# UC3906_3BJT_CHARGER_2.net
KiCad netlist of a schematic drawn in EAGLE
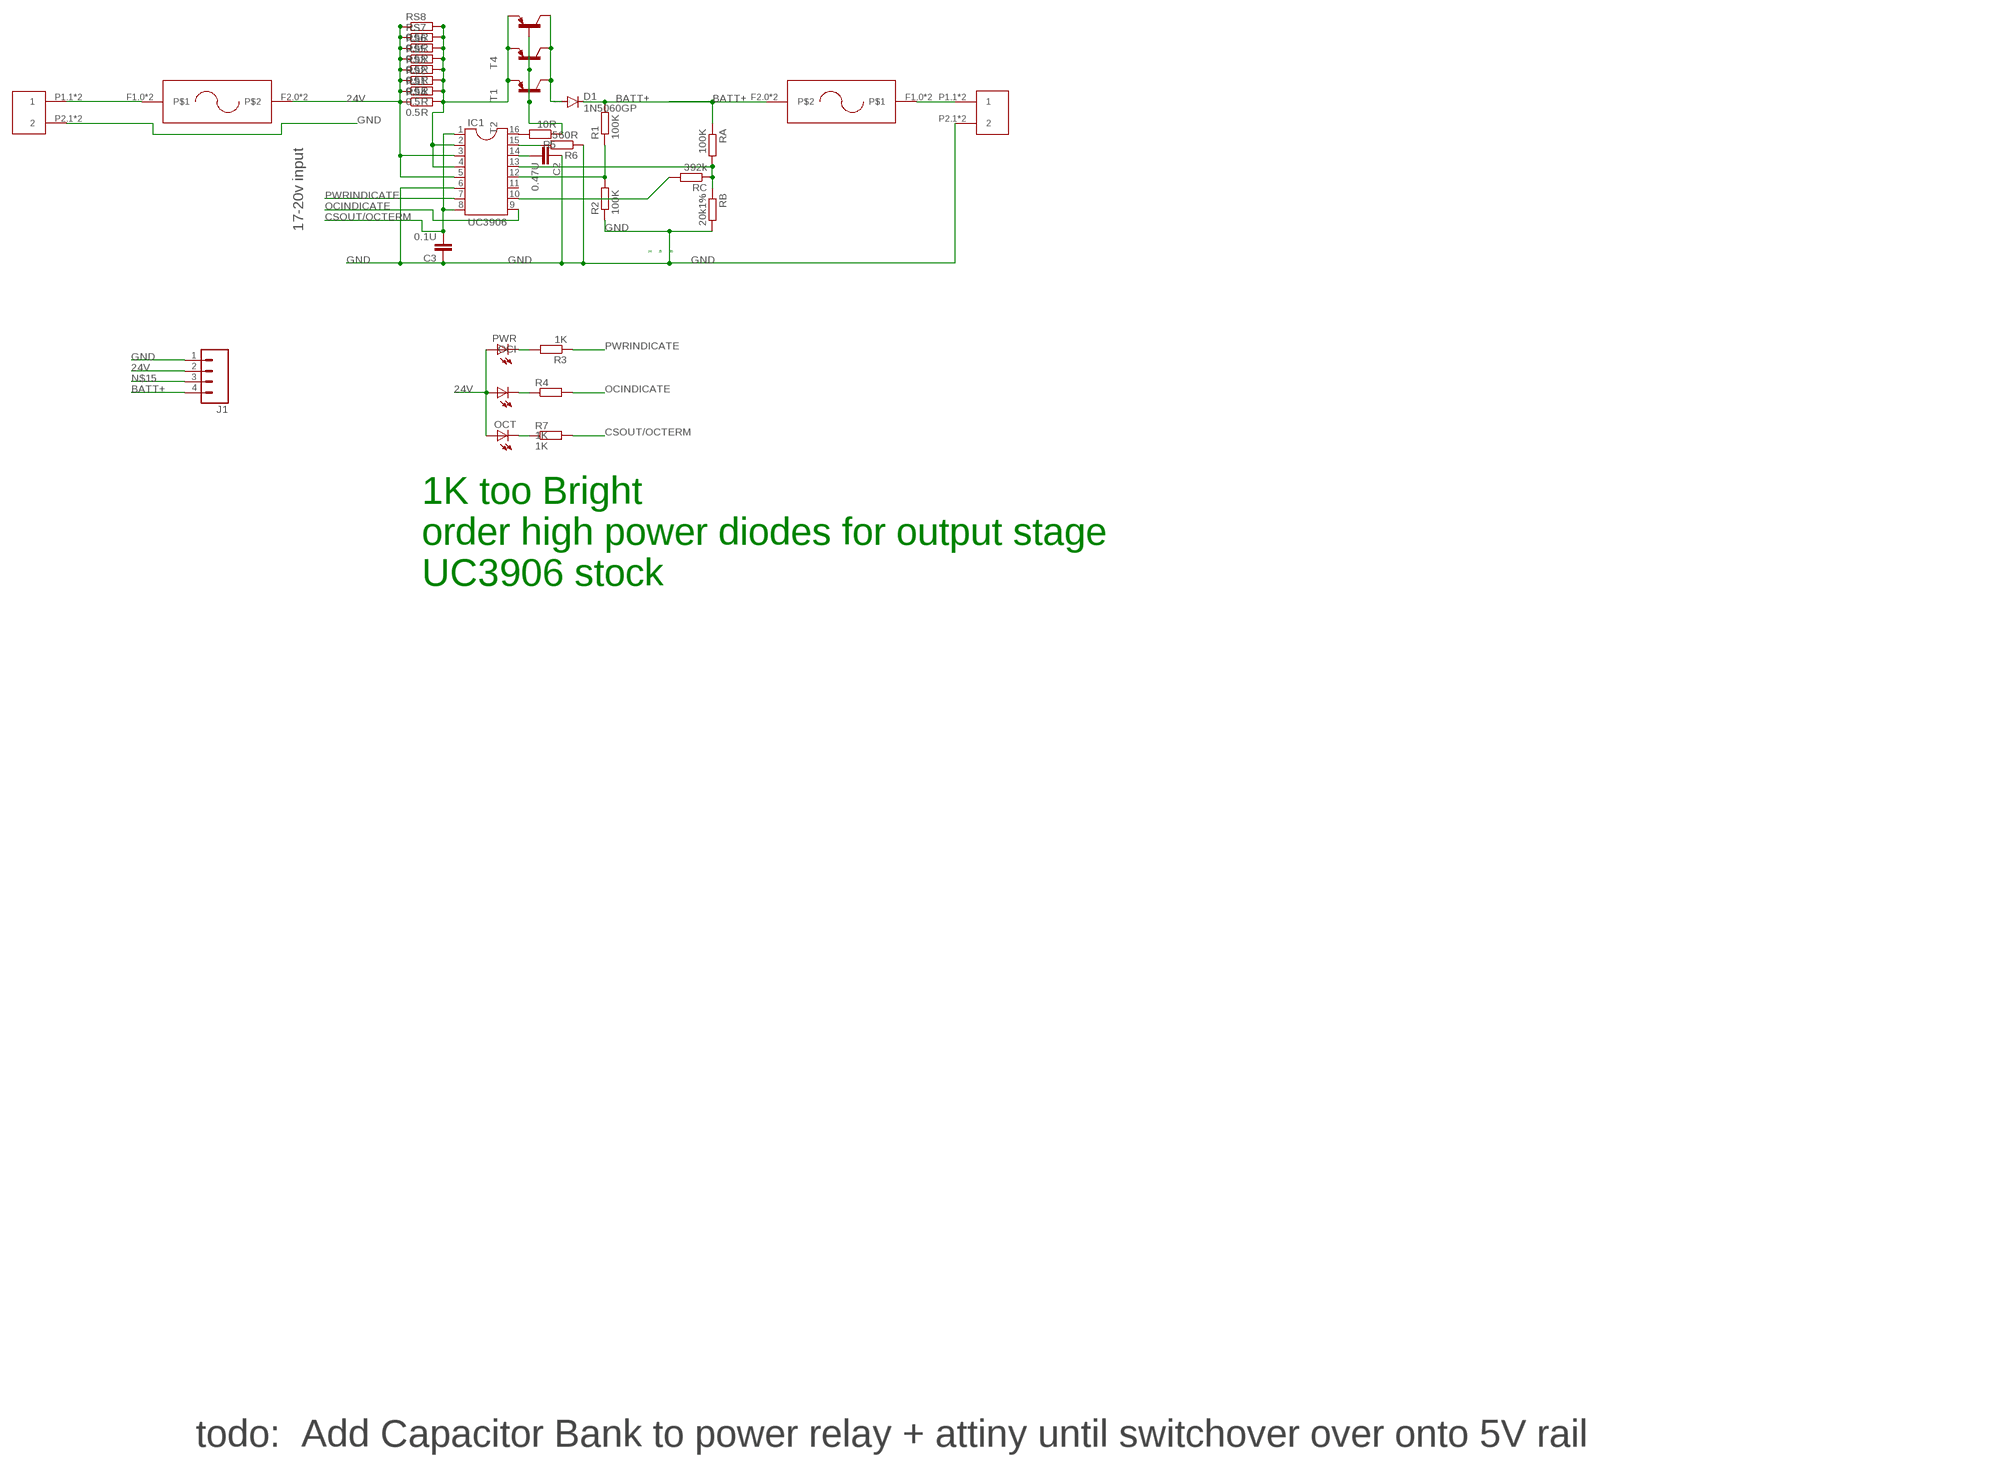
[diagram p0: schematic, sheet 1]

(export (version "E")
  (design (tool "Eeschema 10.0.6"))
  (components
    (comp (ref "BATT")
      (value "BARRIERTERMINAL")
      (footprint "eagle-import:BARRIERTERMINAL")
      (libsource (lib "eagle-import") (part "BARRIERTERMINAL"))
    )
    (comp (ref "C2")
      (value "0.47U")
      (footprint "eagle-import:C050-024X044")
      (libsource (lib "eagle-import") (part "C-EU050-024X044"))
    )
    (comp (ref "C3")
      (value "0.1U")
      (footprint "eagle-import:C050-024X044")
      (libsource (lib "eagle-import") (part "C-EU050-024X044"))
    )
    (comp (ref "D1")
      (value "1N5060GP")
      (footprint "eagle-import:DO15-12")
      (libsource (lib "eagle-import") (part "1N5060GP"))
    )
    (comp (ref "IC1")
      (value "UC3906")
      (footprint "eagle-import:DIL16")
      (libsource (lib "eagle-import") (part "DIL16"))
    )
    (comp (ref "J1")
      (value "CONN_04LONGPADS")
      (footprint "eagle-import:1X04_LONGPADS")
      (libsource (lib "eagle-import") (part "CONN_04LONGPADS"))
    )
    (comp (ref "OCI")
      (value "LED5MM")
      (footprint "eagle-import:LED5MM")
      (libsource (lib "eagle-import") (part "LED5MM"))
    )
    (comp (ref "OCT")
      (value "LED5MM")
      (footprint "eagle-import:LED5MM")
      (libsource (lib "eagle-import") (part "LED5MM"))
    )
    (comp (ref "POWERIN")
      (value "BARRIERTERMINAL")
      (footprint "eagle-import:BARRIERTERMINAL")
      (libsource (lib "eagle-import") (part "BARRIERTERMINAL"))
    )
    (comp (ref "PWR")
      (value "LED5MM")
      (footprint "eagle-import:LED5MM")
      (libsource (lib "eagle-import") (part "LED5MM"))
    )
    (comp (ref "R1")
      (value "100K")
      (footprint "eagle-import:0204_7")
      (libsource (lib "eagle-import") (part "R-EU_0204/7"))
    )
    (comp (ref "R2")
      (value "100K")
      (footprint "eagle-import:0204_7")
      (libsource (lib "eagle-import") (part "R-EU_0204/7"))
    )
    (comp (ref "R3")
      (value "1K")
      (footprint "eagle-import:0204_7")
      (libsource (lib "eagle-import") (part "R-EU_0204/7"))
    )
    (comp (ref "R4")
      (value "1K")
      (footprint "eagle-import:0204_7")
      (libsource (lib "eagle-import") (part "R-EU_0204/7"))
    )
    (comp (ref "R5")
      (value "10R")
      (footprint "eagle-import:0204_7")
      (libsource (lib "eagle-import") (part "R-EU_0204/7"))
    )
    (comp (ref "R6")
      (value "560R")
      (footprint "eagle-import:0204_7")
      (libsource (lib "eagle-import") (part "R-EU_0204/7"))
    )
    (comp (ref "R7")
      (value "1K")
      (footprint "eagle-import:0204_7")
      (libsource (lib "eagle-import") (part "R-EU_0204/7"))
    )
    (comp (ref "RA")
      (value "100K")
      (footprint "eagle-import:0204_7")
      (libsource (lib "eagle-import") (part "R-EU_0204/7"))
    )
    (comp (ref "RB")
      (value "20k1%")
      (footprint "eagle-import:0204_7")
      (libsource (lib "eagle-import") (part "R-EU_0204/7"))
    )
    (comp (ref "RC")
      (value "392k")
      (footprint "eagle-import:0204_7")
      (libsource (lib "eagle-import") (part "R-EU_0204/7"))
    )
    (comp (ref "RS1")
      (value "0.5R")
      (footprint "eagle-import:0411_15")
      (libsource (lib "eagle-import") (part "resistor_R-EU_0411/15"))
    )
    (comp (ref "RS2")
      (value "0.5R")
      (footprint "eagle-import:0411_15")
      (libsource (lib "eagle-import") (part "resistor_R-EU_0411/15"))
    )
    (comp (ref "RS3")
      (value "0.5R")
      (footprint "eagle-import:0411_15")
      (libsource (lib "eagle-import") (part "resistor_R-EU_0411/15"))
    )
    (comp (ref "RS4")
      (value "0.5R")
      (footprint "eagle-import:0411_15")
      (libsource (lib "eagle-import") (part "resistor_R-EU_0411/15"))
    )
    (comp (ref "RS5")
      (value "0.5R")
      (footprint "eagle-import:0411_15")
      (libsource (lib "eagle-import") (part "resistor_R-EU_0411/15"))
    )
    (comp (ref "RS6")
      (value "0.5R")
      (footprint "eagle-import:0411_15")
      (libsource (lib "eagle-import") (part "resistor_R-EU_0411/15"))
    )
    (comp (ref "RS7")
      (value "0.5R")
      (footprint "eagle-import:0411_15")
      (libsource (lib "eagle-import") (part "resistor_R-EU_0411/15"))
    )
    (comp (ref "RS8")
      (value "0.5R")
      (footprint "eagle-import:0411_15")
      (libsource (lib "eagle-import") (part "resistor_R-EU_0411/15"))
    )
    (comp (ref "T1")
      (value "-PNP-TO220V")
      (footprint "eagle-import:TO220V")
      (libsource (lib "eagle-import") (part "-PNP-TO220V"))
    )
    (comp (ref "T2")
      (value "-PNP-TO220V")
      (footprint "eagle-import:TO220V")
      (libsource (lib "eagle-import") (part "-PNP-TO220V"))
    )
    (comp (ref "T4")
      (value "-PNP-TO220V")
      (footprint "eagle-import:TO220V")
      (libsource (lib "eagle-import") (part "-PNP-TO220V"))
    )
    (comp (ref "U$1")
      (value "18MMFUSEHOLDER")
      (footprint "eagle-import:18MMFUSEHOLDER")
      (libsource (lib "eagle-import") (part "18MMFUSEHOLDER"))
    )
    (comp (ref "U$2")
      (value "18MMFUSEHOLDER")
      (footprint "eagle-import:18MMFUSEHOLDER")
      (libsource (lib "eagle-import") (part "18MMFUSEHOLDER"))
    )
  )
  (nets
    (net (code "1") (name "/24V") (class "Default")
      (node (ref "IC1") (pin "3") (pinfunction "3_3") (pintype "passive"))
      (node (ref "IC1") (pin "5") (pinfunction "5_5") (pintype "passive"))
      (node (ref "J1") (pin "2") (pinfunction "2_2") (pintype "passive"))
      (node (ref "OCI") (pin "A") (pinfunction "A_A") (pintype "passive"))
      (node (ref "OCT") (pin "A") (pinfunction "A_A") (pintype "passive"))
      (node (ref "PWR") (pin "A") (pinfunction "A_A") (pintype "passive"))
      (node (ref "RS1") (pin "1") (pinfunction "1_1") (pintype "passive"))
      (node (ref "RS2") (pin "1") (pinfunction "1_1") (pintype "passive"))
      (node (ref "RS3") (pin "1") (pinfunction "1_1") (pintype "passive"))
      (node (ref "RS4") (pin "1") (pinfunction "1_1") (pintype "passive"))
      (node (ref "RS5") (pin "1") (pinfunction "1_1") (pintype "passive"))
      (node (ref "RS6") (pin "1") (pinfunction "1_1") (pintype "passive"))
      (node (ref "RS7") (pin "1") (pinfunction "1_1") (pintype "passive"))
      (node (ref "RS8") (pin "1") (pinfunction "1_1") (pintype "passive"))
      (node (ref "U$2") (pin "F2.0") (pinfunction "P$2_F2.0") (pintype "bidirectional"))
      (node (ref "U$2") (pin "F2.1") (pinfunction "P$2_F2.1") (pintype "bidirectional"))
    )
    (net (code "2") (name "/BATT+") (class "Default")
      (node (ref "D1") (pin "C") (pinfunction "C_C") (pintype "passive"))
      (node (ref "J1") (pin "4") (pinfunction "4_4") (pintype "passive"))
      (node (ref "R1") (pin "2") (pinfunction "2_2") (pintype "passive"))
      (node (ref "RA") (pin "1") (pinfunction "1_1") (pintype "passive"))
      (node (ref "U$1") (pin "F2.0") (pinfunction "P$2_F2.0") (pintype "bidirectional"))
      (node (ref "U$1") (pin "F2.1") (pinfunction "P$2_F2.1") (pintype "bidirectional"))
    )
    (net (code "3") (name "/CSOUT{slash}OCTERM") (class "Default")
      (node (ref "C3") (pin "2") (pinfunction "2_2") (pintype "passive"))
      (node (ref "IC1") (pin "1") (pinfunction "1_1") (pintype "passive"))
      (node (ref "IC1") (pin "8") (pinfunction "8_8") (pintype "passive"))
      (node (ref "R7") (pin "2") (pinfunction "2_2") (pintype "passive"))
    )
    (net (code "4") (name "/GND") (class "Default")
      (node (ref "BATT") (pin "P2.1") (pinfunction "2_P2.1") (pintype "bidirectional"))
      (node (ref "BATT") (pin "P2.2") (pinfunction "2_P2.2") (pintype "bidirectional"))
      (node (ref "C2") (pin "1") (pinfunction "1_1") (pintype "passive"))
      (node (ref "C3") (pin "1") (pinfunction "1_1") (pintype "passive"))
      (node (ref "IC1") (pin "6") (pinfunction "6_6") (pintype "passive"))
      (node (ref "J1") (pin "1") (pinfunction "1_1") (pintype "passive"))
      (node (ref "POWERIN") (pin "P2.1") (pinfunction "2_P2.1") (pintype "bidirectional"))
      (node (ref "POWERIN") (pin "P2.2") (pinfunction "2_P2.2") (pintype "bidirectional"))
      (node (ref "R2") (pin "1") (pinfunction "1_1") (pintype "passive"))
      (node (ref "R6") (pin "1") (pinfunction "1_1") (pintype "passive"))
      (node (ref "RB") (pin "2") (pinfunction "2_2") (pintype "passive"))
    )
    (net (code "5") (name "/N$15") (class "Default")
      (node (ref "D1") (pin "A") (pinfunction "A_A") (pintype "passive"))
      (node (ref "J1") (pin "3") (pinfunction "3_3") (pintype "passive"))
      (node (ref "T1") (pin "2") (pinfunction "C_2") (pintype "passive"))
      (node (ref "T2") (pin "2") (pinfunction "C_2") (pintype "passive"))
      (node (ref "T4") (pin "2") (pinfunction "C_2") (pintype "passive"))
    )
    (net (code "6") (name "/OCINDICATE") (class "Default")
      (node (ref "IC1") (pin "9") (pinfunction "9_9") (pintype "passive"))
      (node (ref "R4") (pin "2") (pinfunction "2_2") (pintype "passive"))
    )
    (net (code "7") (name "/PWRINDICATE") (class "Default")
      (node (ref "IC1") (pin "7") (pinfunction "7_7") (pintype "passive"))
      (node (ref "R3") (pin "1") (pinfunction "1_1") (pintype "passive"))
    )
    (net (code "8") (name "Net-(BATT-1-PadP1.1)") (class "Default")
      (node (ref "BATT") (pin "P1.1") (pinfunction "1_P1.1") (pintype "bidirectional"))
      (node (ref "BATT") (pin "P1.2") (pinfunction "1_P1.2") (pintype "bidirectional"))
      (node (ref "U$1") (pin "F1.0") (pinfunction "P$1_F1.0") (pintype "bidirectional"))
      (node (ref "U$1") (pin "F1.1") (pinfunction "P$1_F1.1") (pintype "bidirectional"))
    )
    (net (code "9") (name "Net-(C2-Pad2)") (class "Default")
      (node (ref "C2") (pin "2") (pinfunction "2_2") (pintype "passive"))
      (node (ref "IC1") (pin "14") (pinfunction "14_14") (pintype "passive"))
    )
    (net (code "10") (name "Net-(IC1-Pad10)") (class "Default")
      (node (ref "IC1") (pin "10") (pinfunction "10_10") (pintype "passive"))
      (node (ref "RC") (pin "2") (pinfunction "2_2") (pintype "passive"))
    )
    (net (code "11") (name "Net-(IC1-Pad12)") (class "Default")
      (node (ref "IC1") (pin "12") (pinfunction "12_12") (pintype "passive"))
      (node (ref "R1") (pin "1") (pinfunction "1_1") (pintype "passive"))
      (node (ref "R2") (pin "2") (pinfunction "2_2") (pintype "passive"))
    )
    (net (code "12") (name "Net-(IC1-Pad13)") (class "Default")
      (node (ref "IC1") (pin "13") (pinfunction "13_13") (pintype "passive"))
      (node (ref "RA") (pin "2") (pinfunction "2_2") (pintype "passive"))
      (node (ref "RB") (pin "1") (pinfunction "1_1") (pintype "passive"))
      (node (ref "RC") (pin "1") (pinfunction "1_1") (pintype "passive"))
    )
    (net (code "13") (name "Net-(IC1-Pad15)") (class "Default")
      (node (ref "IC1") (pin "15") (pinfunction "15_15") (pintype "passive"))
      (node (ref "R6") (pin "2") (pinfunction "2_2") (pintype "passive"))
    )
    (net (code "14") (name "Net-(IC1-Pad16)") (class "Default")
      (node (ref "IC1") (pin "16") (pinfunction "16_16") (pintype "passive"))
      (node (ref "R5") (pin "2") (pinfunction "2_2") (pintype "passive"))
    )
    (net (code "15") (name "Net-(OCI-C)") (class "Default")
      (node (ref "OCI") (pin "K") (pinfunction "C_K") (pintype "passive"))
      (node (ref "R4") (pin "1") (pinfunction "1_1") (pintype "passive"))
    )
    (net (code "16") (name "Net-(OCT-C)") (class "Default")
      (node (ref "OCT") (pin "K") (pinfunction "C_K") (pintype "passive"))
      (node (ref "R7") (pin "1") (pinfunction "1_1") (pintype "passive"))
    )
    (net (code "17") (name "Net-(POWERIN-1-PadP1.1)") (class "Default")
      (node (ref "POWERIN") (pin "P1.1") (pinfunction "1_P1.1") (pintype "bidirectional"))
      (node (ref "POWERIN") (pin "P1.2") (pinfunction "1_P1.2") (pintype "bidirectional"))
      (node (ref "U$2") (pin "F1.0") (pinfunction "P$1_F1.0") (pintype "bidirectional"))
      (node (ref "U$2") (pin "F1.1") (pinfunction "P$1_F1.1") (pintype "bidirectional"))
    )
    (net (code "18") (name "Net-(PWR-C)") (class "Default")
      (node (ref "PWR") (pin "K") (pinfunction "C_K") (pintype "passive"))
      (node (ref "R3") (pin "2") (pinfunction "2_2") (pintype "passive"))
    )
    (net (code "19") (name "Net-(T1-B)") (class "Default")
      (node (ref "R5") (pin "1") (pinfunction "1_1") (pintype "passive"))
      (node (ref "T1") (pin "1") (pinfunction "B_1") (pintype "passive"))
      (node (ref "T2") (pin "1") (pinfunction "B_1") (pintype "passive"))
      (node (ref "T4") (pin "1") (pinfunction "B_1") (pintype "passive"))
    )
    (net (code "20") (name "Net-(T1-E)") (class "Default")
      (node (ref "IC1") (pin "2") (pinfunction "2_2") (pintype "passive"))
      (node (ref "IC1") (pin "4") (pinfunction "4_4") (pintype "passive"))
      (node (ref "RS1") (pin "2") (pinfunction "2_2") (pintype "passive"))
      (node (ref "RS2") (pin "2") (pinfunction "2_2") (pintype "passive"))
      (node (ref "RS3") (pin "2") (pinfunction "2_2") (pintype "passive"))
      (node (ref "RS4") (pin "2") (pinfunction "2_2") (pintype "passive"))
      (node (ref "RS5") (pin "2") (pinfunction "2_2") (pintype "passive"))
      (node (ref "RS6") (pin "2") (pinfunction "2_2") (pintype "passive"))
      (node (ref "RS7") (pin "2") (pinfunction "2_2") (pintype "passive"))
      (node (ref "RS8") (pin "2") (pinfunction "2_2") (pintype "passive"))
      (node (ref "T1") (pin "3") (pinfunction "E_3") (pintype "passive"))
      (node (ref "T2") (pin "3") (pinfunction "E_3") (pintype "passive"))
      (node (ref "T4") (pin "3") (pinfunction "E_3") (pintype "passive"))
    )
    (net (code "21") (name "unconnected-(IC1-Pad11)") (class "Default")
      (node (ref "IC1") (pin "11") (pinfunction "11_11") (pintype "passive"))
    )
  )
)
